# Tutorial_Sheet.net
KiCad netlist of a schematic drawn in Altium Designer
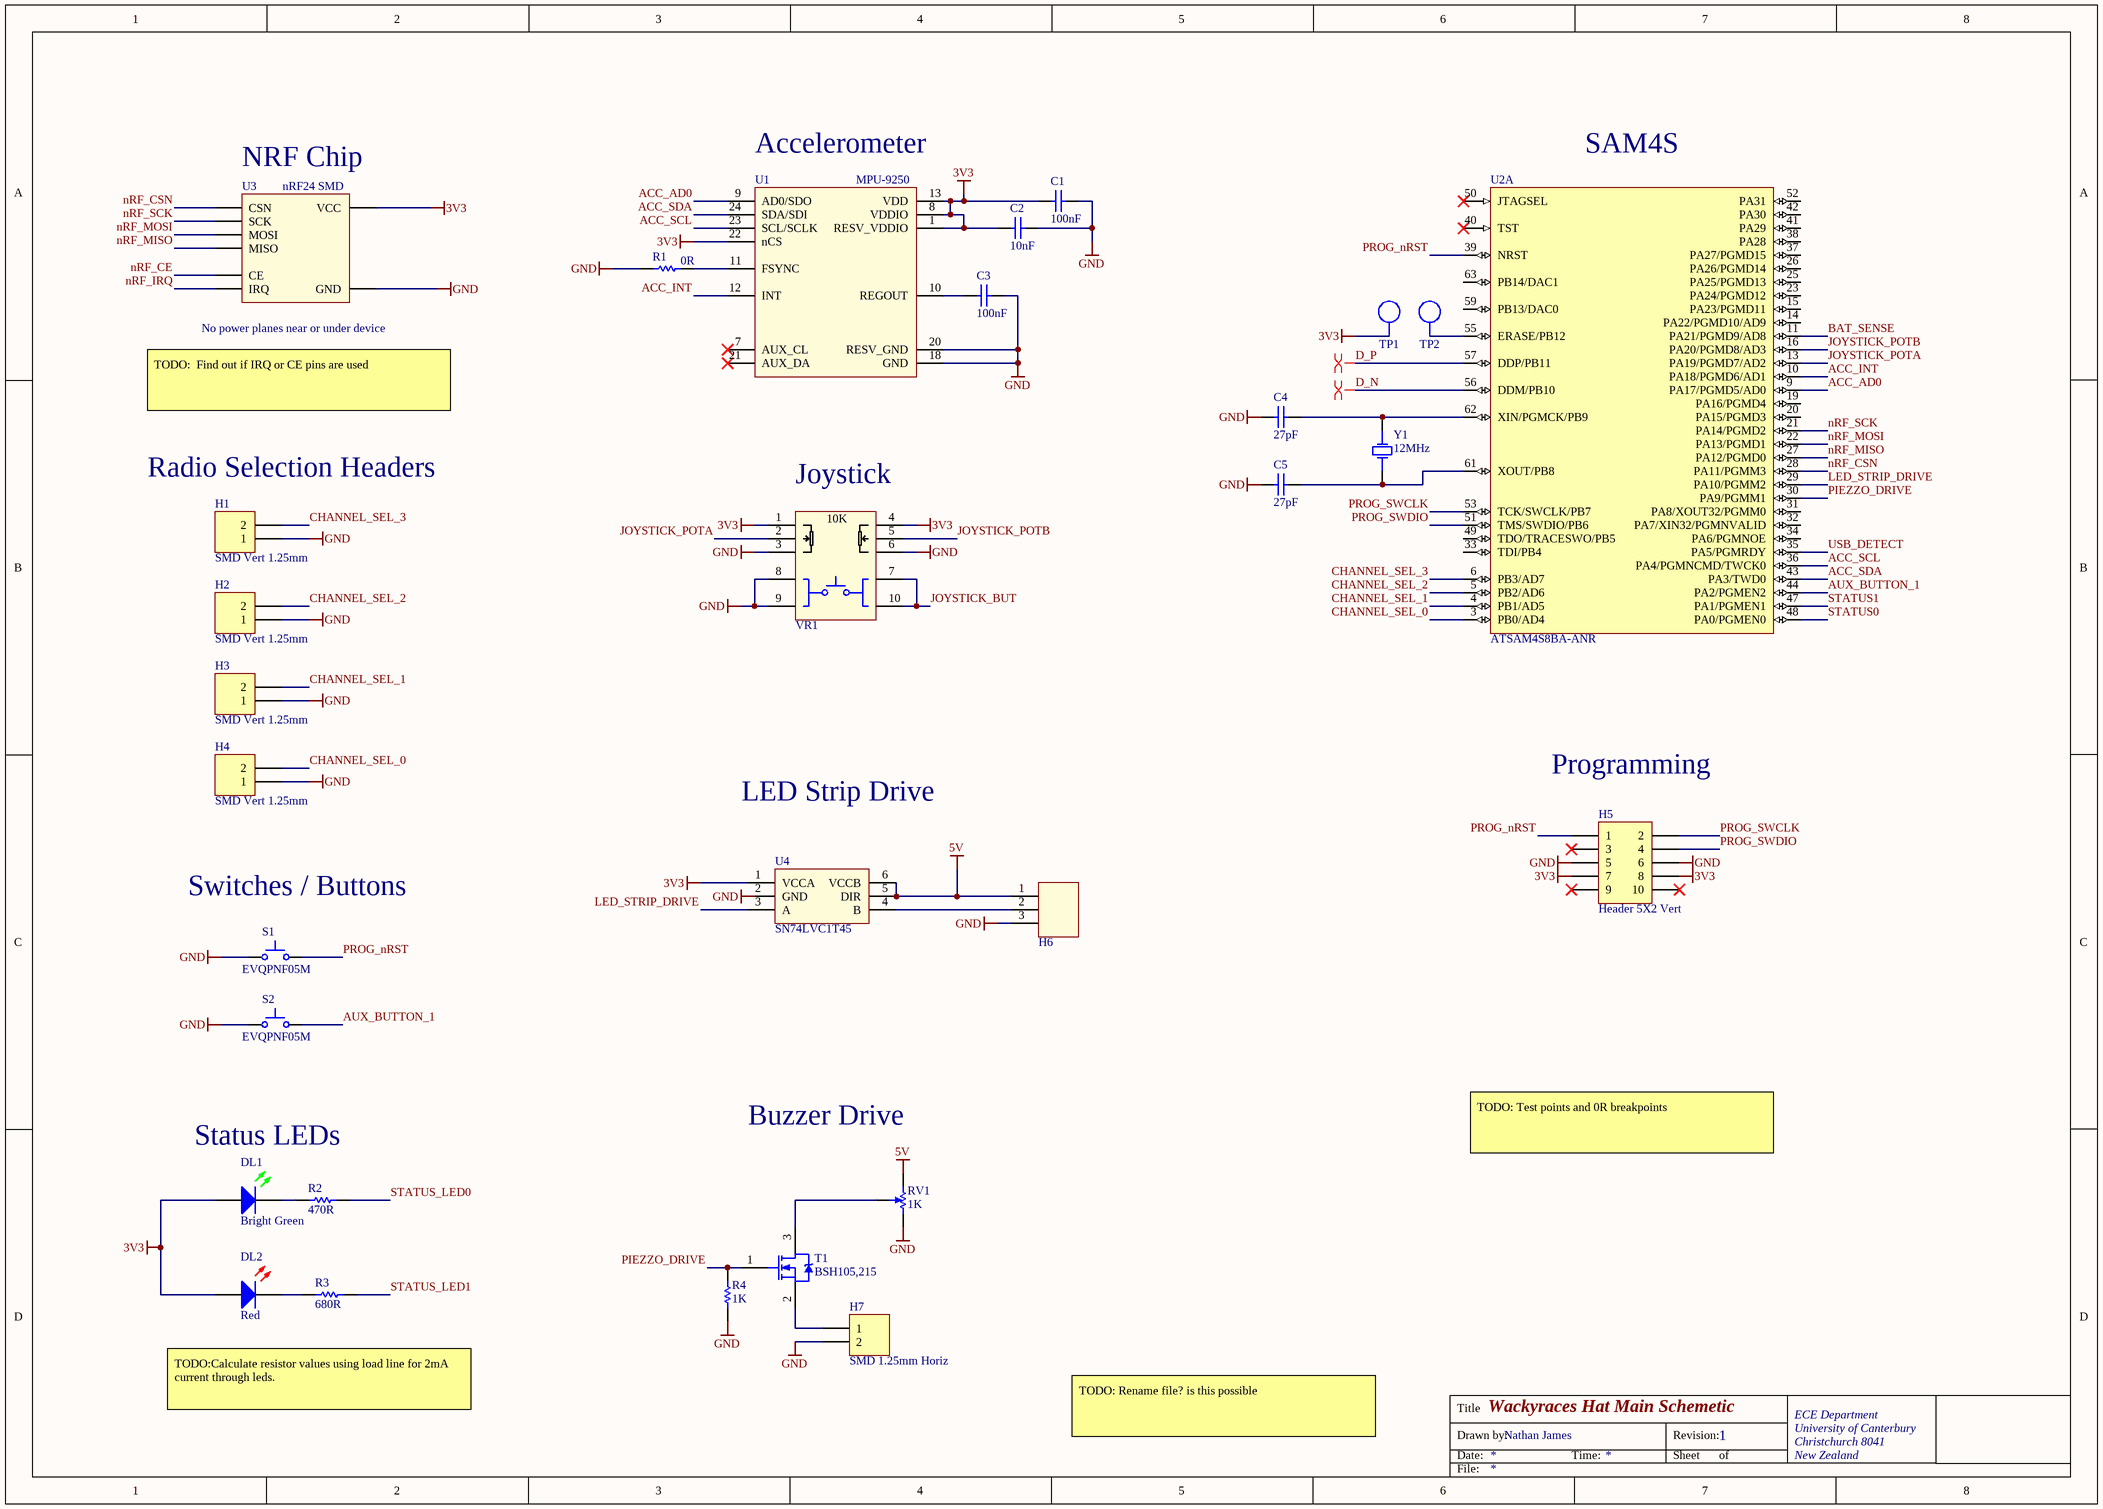
[diagram p0: Tutorial Sheet.SchDoc]

(export (version "E")
  (design (tool "Eeschema 10.0.6"))
  (components
    (comp (ref "C1")
      (value "100nF")
      (footprint "CAPC1608L")
      (description "CAP CER 100nF X7R +-10% 50V 0603")
      (libsource (lib "ECE AD19Components_19V1") (part "CC_100nF_0603"))
    )
    (comp (ref "C2")
      (value "10nF")
      (footprint "CAPC1608L")
      (description "CAP CER 10nF X7R +-10% 50V 0603")
      (libsource (lib "ECE AD19Components_19V1") (part "CC_10nF_0603"))
    )
    (comp (ref "C3")
      (value "100nF")
      (footprint "CAPC1608L")
      (description "CAP CER 100nF X7R +-10% 50V 0603")
      (libsource (lib "ECE AD19Components_19V1") (part "CC_100nF_0603"))
    )
    (comp (ref "C4")
      (value "27pF")
      (footprint "CAPC1608L")
      (description "CAP CER 27pF NPO/COG +-5% 50V 0603")
      (libsource (lib "ECE AD19Components_19V1") (part "CC_27pF_0603"))
    )
    (comp (ref "C5")
      (value "27pF")
      (footprint "CAPC1608L")
      (description "CAP CER 27pF NPO/COG +-5% 50V 0603")
      (libsource (lib "ECE AD19Components_19V1") (part "CC_27pF_0603"))
    )
    (comp (ref "DL1")
      (value "Bright Green")
      (footprint "WL-SMCW0603")
      (description "LED Bright Green 40mcd 0603 SMD")
      (fields
        (field (name "MANUFACTURER") "WURTH ELEKTRONIK")
        (field (name "MANUFACTURER PART NUMBER") "150060VS75000")
        (field (name "LED COLOUR") "Bright Green")
      )
      (libsource (lib "ECE AD19Components_19V1") (part "DL_150060VS75000"))
    )
    (comp (ref "DL2")
      (value "Red")
      (footprint "WL-SMCW0603")
      (description "LED Red 250mcd 0603 SMD")
      (fields
        (field (name "MANUFACTURER") "WURTH ELEKTRONIK")
        (field (name "MANUFACTURER PART NUMBER") "150060RS75000")
        (field (name "LED COLOUR") "Red")
      )
      (libsource (lib "ECE AD19Components_19V1") (part "DL_150060RS75000"))
    )
    (comp (ref "H1")
      (value "SMD Vert 1.25mm")
      (footprint "SD-53398-0219")
      (description "Header_Vert_2Pos_1.25mm_125V@1A_SMT")
      (fields
        (field (name "MANUFACTURER") "Molex Inc")
        (field (name "MANUFACTURER PART NUMBER") "0533980271")
      )
      (libsource (lib "ECE AD19Components_19V1") (part "JB_53398-02"))
    )
    (comp (ref "H2")
      (value "SMD Vert 1.25mm")
      (footprint "SD-53398-0219")
      (description "Header_Vert_2Pos_1.25mm_125V@1A_SMT")
      (fields
        (field (name "MANUFACTURER") "Molex Inc")
        (field (name "MANUFACTURER PART NUMBER") "0533980271")
      )
      (libsource (lib "ECE AD19Components_19V1") (part "JB_53398-02"))
    )
    (comp (ref "H3")
      (value "SMD Vert 1.25mm")
      (footprint "SD-53398-0219")
      (description "Header_Vert_2Pos_1.25mm_125V@1A_SMT")
      (fields
        (field (name "MANUFACTURER") "Molex Inc")
        (field (name "MANUFACTURER PART NUMBER") "0533980271")
      )
      (libsource (lib "ECE AD19Components_19V1") (part "JB_53398-02"))
    )
    (comp (ref "H4")
      (value "SMD Vert 1.25mm")
      (footprint "SD-53398-0219")
      (description "Header_Vert_2Pos_1.25mm_125V@1A_SMT")
      (fields
        (field (name "MANUFACTURER") "Molex Inc")
        (field (name "MANUFACTURER PART NUMBER") "0533980271")
      )
      (libsource (lib "ECE AD19Components_19V1") (part "JB_53398-02"))
    )
    (comp (ref "H5")
      (value "Header 5X2 Vert")
      (footprint "IDC2.54-V10D")
      (description "IDC Header, 2,54mm, 10-Pin, Vert")
      (libsource (lib "ECE AD19Components_19V1") (part "JA_HDR_IDC_5X2_VERT"))
    )
    (comp (ref "H6")
      (value "HEADER_3")
      (footprint "HEADER_3POS")
      (description "3Pin Header 2.54mm spacing")
      (libsource (lib "ENCE461AD19_19V2") (part "HEADER_3"))
    )
    (comp (ref "H7")
      (value "SMD 1.25mm Horiz")
      (footprint "SD-53261-0219")
      (description "Header_Horiz_2Pos_1.25mm_125V@1A_SMT")
      (fields (field (name "MANUFACTURER") "MOLEX") (field (name "MANUFACTURER PART NUMBER") "53261-0271"))
      (libsource (lib "ECE AD19Components_19V1") (part "JB_53261-02"))
    )
    (comp (ref "R1")
      (value "0R")
      (footprint "RESC1608L")
      (description "RES 0.0 OHM 1/10W 5% 0603 SMD")
      (libsource (lib "ECE AD19Components_19V1") (part "RS_0R0"))
    )
    (comp (ref "R2")
      (value "470R")
      (footprint "RESC1608L")
      (description "RES 470 OHM 1/10W 5% 0603 SMD")
      (libsource (lib "ECE AD19Components_19V1") (part "RS_470R"))
    )
    (comp (ref "R3")
      (value "680R")
      (footprint "RESC3216L")
      (description "RES 680R OHM 1/4W 5% 1206 SMD")
      (libsource (lib "ECE AD19Components_19V1") (part "RT_680R"))
    )
    (comp (ref "R4")
      (value "1K")
      (footprint "RESC1608L")
      (description "RES 1.0K OHM 1/10W 5% 0603 SMD")
      (libsource (lib "ECE AD19Components_19V1") (part "RS_1K"))
    )
    (comp (ref "RV1")
      (value "1K")
      (footprint "PVZ2A")
      (description "Trim Pot SMD 1K Murata PVZ2 Series SMD")
      (fields
        (field (name "MANUFACTURER") "MURATA")
        (field (name "MANUFACTURER PART NUMBER") "PVZ2A102C04B00")
      )
      (libsource (lib "ECE AD19Components_19V1") (part "RM_1K"))
    )
    (comp (ref "S1")
      (value "EVQPNF05M")
      (footprint "EVQPNF05M")
      (description "Panasonic 6 x 3.5mm SMD Light Touch Switch Type SMD")
      (fields (field (name "MANUFACTURER") "Panasonic"))
      (libsource (lib "ECE AD19Components_19V1") (part "WS_EVQPNF05M"))
    )
    (comp (ref "S2")
      (value "EVQPNF05M")
      (footprint "EVQPNF05M")
      (description "Panasonic 6 x 3.5mm SMD Light Touch Switch Type SMD")
      (fields (field (name "MANUFACTURER") "Panasonic"))
      (libsource (lib "ECE AD19Components_19V1") (part "WS_EVQPNF05M"))
    )
    (comp (ref "T1")
      (value "BSH105,215")
      (footprint "SOT23_L")
      (description "MOSFET N-CH 20V 1.05A SOT-23")
      (fields
        (field (name "MANUFACTURER") "NXP Semiconductors")
        (field (name "MANUFACTURER PART NUMBER") "BSH105,215")
      )
      (libsource (lib "ECE AD19Components_19V1") (part "TM_BSH105"))
    )
    (comp (ref "TP1")
      (value "Erase")
      (footprint "TP_1206")
      (description "Test-Point 3.3x1.6x2.1mm SMD")
      (fields
        (field (name "MANUFACTURER") "Harwin Inc")
        (field (name "MANUFACTURER PART NUMBER") "S1751-46R")
      )
      (libsource (lib "ECE AD19Components_19V1") (part "TP_1206"))
    )
    (comp (ref "TP2")
      (value "Erase")
      (footprint "TP_1206")
      (description "Test-Point 3.3x1.6x2.1mm SMD")
      (fields
        (field (name "MANUFACTURER") "Harwin Inc")
        (field (name "MANUFACTURER PART NUMBER") "S1751-46R")
      )
      (libsource (lib "ECE AD19Components_19V1") (part "TP_1206"))
    )
    (comp (ref "U1")
      (value "MPU-9250")
      (footprint "Quad24")
      (description "9 axis IMU")
      (libsource (lib "ENCE461AD19_19V2") (part "MPU-9250"))
    )
    (comp (ref "U2")
      (value "ATSAM4S8BA-ANR")
      (footprint "LQFP64_L")
      (description "IC MCU 32BIT 512KB FLASH 64LQFP")
      (fields (field (name "MANUFACTURER") "Atmel"))
      (libsource (lib "ECE AD19Components_19V1") (part "SE_ATSAM4S16BA-MU"))
    )
    (comp (ref "U3")
      (value "nRF24 SMD")
      (footprint "NRF24")
      (description "nRF24 SMD Module")
      (fields (field (name "WARNING") "No power planes near or under device"))
      (libsource (lib "ENCE461AD19_19V2") (part "NRF24"))
    )
    (comp (ref "U4")
      (value "SN74LVC1T45")
      (footprint "SOT23-6_N")
      (description "1.8V - 5V level converter")
      (libsource (lib "ENCE461_extras_2020") (part "SN74LVC1T45"))
    )
    (comp (ref "VR1")
      (value "Joystick 10k with Sw")
      (footprint "Joystick_Sw")
      (description "JOYSTICK 10K OHM 2 AXIS TH")
      (libsource (lib "ENCE461AD19_19V2") (part "Joystick 10k with Sw"))
    )
    (comp (ref "Y1")
      (value "12MHz")
      (footprint "6.0X3.5-4")
      (description "CRYSTAL 12MHZ 18PF 6X3.5mm SMD")
      (fields
        (field (name "MANUFACTURER") "CTS-Frequency Controls")
        (field (name "MANUFACTURER PART NUMBER") "406C35D12M00000")
        (field (name "FREQUENCY") "12MHz")
      )
      (libsource (lib "ECE AD19Components_19V1") (part "XT_CRYSTAL_12MHz_18pF"))
    )
  )
  (nets
    (net (code "1") (name "/ACC_AD0") (class "Default")
      (node (ref "U1") (pin "9") (pinfunction "AD0/SDO_9") (pintype "passive"))
      (node (ref "U2") (pin "9") (pinfunction "PA17/PGMD5/AD0_9") (pintype "bidirectional"))
    )
    (net (code "2") (name "/ACC_INT") (class "Default")
      (node (ref "U1") (pin "12") (pinfunction "INT_12") (pintype "passive"))
      (node (ref "U2") (pin "10") (pinfunction "PA18/PGMD6/AD1_10") (pintype "bidirectional"))
    )
    (net (code "3") (name "/ACC_SCL") (class "Default")
      (node (ref "U1") (pin "23") (pinfunction "SCL/SCLK_23") (pintype "passive"))
      (node (ref "U2") (pin "36") (pinfunction "PA4/PGMNCMD/TWCK0_36") (pintype "bidirectional"))
    )
    (net (code "4") (name "/ACC_SDA") (class "Default")
      (node (ref "U1") (pin "24") (pinfunction "SDA/SDI_24") (pintype "passive"))
      (node (ref "U2") (pin "43") (pinfunction "PA3/TWD0_43") (pintype "bidirectional"))
    )
    (net (code "5") (name "/AUX_BUTTON_1") (class "Default")
      (node (ref "S2") (pin "2") (pintype "passive"))
      (node (ref "U2") (pin "44") (pinfunction "PA2/PGMEN2_44") (pintype "bidirectional"))
    )
    (net (code "6") (name "/BAT_SENSE") (class "Default")
      (node (ref "U2") (pin "11") (pinfunction "PA21/PGMD9/AD8_11") (pintype "bidirectional"))
    )
    (net (code "7") (name "/CHANNEL_SEL_0") (class "Default")
      (node (ref "H4") (pin "2") (pinfunction "2_2") (pintype "passive"))
      (node (ref "U2") (pin "3") (pinfunction "PB0/AD4_3") (pintype "bidirectional"))
    )
    (net (code "8") (name "/CHANNEL_SEL_1") (class "Default")
      (node (ref "H3") (pin "2") (pinfunction "2_2") (pintype "passive"))
      (node (ref "U2") (pin "4") (pinfunction "PB1/AD5_4") (pintype "bidirectional"))
    )
    (net (code "9") (name "/CHANNEL_SEL_2") (class "Default")
      (node (ref "H2") (pin "2") (pinfunction "2_2") (pintype "passive"))
      (node (ref "U2") (pin "5") (pinfunction "PB2/AD6_5") (pintype "bidirectional"))
    )
    (net (code "10") (name "/CHANNEL_SEL_3") (class "Default")
      (node (ref "H1") (pin "2") (pinfunction "2_2") (pintype "passive"))
      (node (ref "U2") (pin "6") (pinfunction "PB3/AD7_6") (pintype "bidirectional"))
    )
    (net (code "11") (name "/D_N") (class "Default")
      (node (ref "U2") (pin "56") (pinfunction "DDM/PB10_56") (pintype "bidirectional"))
    )
    (net (code "12") (name "/D_P") (class "Default")
      (node (ref "U2") (pin "57") (pinfunction "DDP/PB11_57") (pintype "bidirectional"))
    )
    (net (code "13") (name "/JOYSTICK_BUT") (class "Default")
      (node (ref "VR1") (pin "10") (pinfunction "10_10") (pintype "passive"))
      (node (ref "VR1") (pin "7") (pinfunction "7_7") (pintype "passive"))
    )
    (net (code "14") (name "/JOYSTICK_POTA") (class "Default")
      (node (ref "U2") (pin "13") (pinfunction "PA19/PGMD7/AD2_13") (pintype "bidirectional"))
      (node (ref "VR1") (pin "2") (pinfunction "2_2") (pintype "passive"))
    )
    (net (code "15") (name "/JOYSTICK_POTB") (class "Default")
      (node (ref "U2") (pin "16") (pinfunction "PA20/PGMD8/AD3_16") (pintype "bidirectional"))
      (node (ref "VR1") (pin "5") (pinfunction "2'_5") (pintype "passive"))
    )
    (net (code "16") (name "/LED_STRIP_DRIVE") (class "Default")
      (node (ref "U2") (pin "29") (pinfunction "PA10/PGMM2_29") (pintype "bidirectional"))
      (node (ref "U4") (pin "3") (pinfunction "A_3") (pintype "passive"))
    )
    (net (code "17") (name "/PIEZZO_DRIVE") (class "Default")
      (node (ref "R4") (pin "2") (pinfunction "2_2") (pintype "passive"))
      (node (ref "T1") (pin "1") (pinfunction "1_1") (pintype "passive"))
      (node (ref "U2") (pin "30") (pinfunction "PA9/PGMM1_30") (pintype "bidirectional"))
    )
    (net (code "18") (name "/PROG_SWCLK") (class "Default")
      (node (ref "H5") (pin "2") (pinfunction "2_2") (pintype "passive"))
      (node (ref "U2") (pin "53") (pinfunction "TCK/SWCLK/PB7_53") (pintype "bidirectional"))
    )
    (net (code "19") (name "/PROG_SWDIO") (class "Default")
      (node (ref "H5") (pin "4") (pinfunction "4_4") (pintype "passive"))
      (node (ref "U2") (pin "51") (pinfunction "TMS/SWDIO/PB6_51") (pintype "bidirectional"))
    )
    (net (code "20") (name "/PROG_nRST") (class "Default")
      (node (ref "H5") (pin "1") (pinfunction "1_1") (pintype "passive"))
      (node (ref "S1") (pin "2") (pintype "passive"))
      (node (ref "U2") (pin "39") (pinfunction "NRST_39") (pintype "bidirectional"))
    )
    (net (code "21") (name "/STATUS0") (class "Default")
      (node (ref "U2") (pin "48") (pinfunction "PA0/PGMEN0_48") (pintype "bidirectional"))
    )
    (net (code "22") (name "/STATUS1") (class "Default")
      (node (ref "U2") (pin "47") (pinfunction "PA1/PGMEN1_47") (pintype "bidirectional"))
    )
    (net (code "23") (name "/STATUS_LED0") (class "Default")
      (node (ref "R2") (pin "2") (pinfunction "2_2") (pintype "passive"))
    )
    (net (code "24") (name "/STATUS_LED1") (class "Default")
      (node (ref "R3") (pin "2") (pinfunction "2_2") (pintype "passive"))
    )
    (net (code "25") (name "/USB_DETECT") (class "Default")
      (node (ref "U2") (pin "35") (pinfunction "PA5/PGMRDY_35") (pintype "bidirectional"))
    )
    (net (code "26") (name "/nRF_CE") (class "Default")
      (node (ref "U3") (pin "3") (pinfunction "CE_3") (pintype "passive"))
    )
    (net (code "27") (name "/nRF_CSN") (class "Default")
      (node (ref "U2") (pin "28") (pinfunction "PA11/PGMM3_28") (pintype "bidirectional"))
      (node (ref "U3") (pin "4") (pinfunction "CSN_4") (pintype "passive"))
    )
    (net (code "28") (name "/nRF_IRQ") (class "Default")
      (node (ref "U3") (pin "8") (pinfunction "IRQ_8") (pintype "passive"))
    )
    (net (code "29") (name "/nRF_MISO") (class "Default")
      (node (ref "U2") (pin "27") (pinfunction "PA12/PGMD0_27") (pintype "bidirectional"))
      (node (ref "U3") (pin "7") (pinfunction "MISO_7") (pintype "passive"))
    )
    (net (code "30") (name "/nRF_MOSI") (class "Default")
      (node (ref "U2") (pin "22") (pinfunction "PA13/PGMD1_22") (pintype "bidirectional"))
      (node (ref "U3") (pin "6") (pinfunction "MOSI_6") (pintype "passive"))
    )
    (net (code "31") (name "/nRF_SCK") (class "Default")
      (node (ref "U2") (pin "21") (pinfunction "PA14/PGMD2_21") (pintype "bidirectional"))
      (node (ref "U3") (pin "5") (pinfunction "SCK_5") (pintype "passive"))
    )
    (net (code "32") (name "3V3") (class "Default")
      (node (ref "C1") (pin "1") (pinfunction "1_1") (pintype "passive"))
      (node (ref "C2") (pin "1") (pinfunction "1_1") (pintype "passive"))
      (node (ref "DL1") (pin "2") (pinfunction "A_2") (pintype "passive"))
      (node (ref "DL2") (pin "2") (pinfunction "A_2") (pintype "passive"))
      (node (ref "H5") (pin "7") (pinfunction "7_7") (pintype "passive"))
      (node (ref "H5") (pin "8") (pinfunction "8_8") (pintype "passive"))
      (node (ref "TP1") (pin "1") (pinfunction "1_1") (pintype "passive"))
      (node (ref "U1") (pin "1") (pinfunction "RESV_VDDIO_1") (pintype "passive"))
      (node (ref "U1") (pin "13") (pinfunction "VDD_13") (pintype "passive"))
      (node (ref "U1") (pin "22") (pinfunction "nCS_22") (pintype "passive"))
      (node (ref "U1") (pin "8") (pinfunction "VDDIO_8") (pintype "passive"))
      (node (ref "U3") (pin "1") (pinfunction "VCC_1") (pintype "passive"))
      (node (ref "U4") (pin "1") (pinfunction "VCCA_1") (pintype "passive"))
      (node (ref "VR1") (pin "1") (pinfunction "1_1") (pintype "passive"))
      (node (ref "VR1") (pin "4") (pinfunction "1'_4") (pintype "passive"))
    )
    (net (code "33") (name "5V") (class "Default")
      (node (ref "H6") (pin "1") (pintype "passive"))
      (node (ref "RV1") (pin "3") (pinfunction "-_3") (pintype "passive"))
      (node (ref "U4") (pin "5") (pinfunction "DIR_5") (pintype "passive"))
      (node (ref "U4") (pin "6") (pinfunction "VCCB_6") (pintype "passive"))
    )
    (net (code "34") (name "GND") (class "Default")
      (node (ref "C1") (pin "2") (pinfunction "2_2") (pintype "passive"))
      (node (ref "C2") (pin "2") (pinfunction "2_2") (pintype "passive"))
      (node (ref "C3") (pin "2") (pinfunction "2_2") (pintype "passive"))
      (node (ref "C4") (pin "1") (pinfunction "1_1") (pintype "passive"))
      (node (ref "C5") (pin "1") (pinfunction "1_1") (pintype "passive"))
      (node (ref "H1") (pin "1") (pinfunction "1_1") (pintype "passive"))
      (node (ref "H2") (pin "1") (pinfunction "1_1") (pintype "passive"))
      (node (ref "H3") (pin "1") (pinfunction "1_1") (pintype "passive"))
      (node (ref "H4") (pin "1") (pinfunction "1_1") (pintype "passive"))
      (node (ref "H5") (pin "5") (pinfunction "5_5") (pintype "passive"))
      (node (ref "H5") (pin "6") (pinfunction "6_6") (pintype "passive"))
      (node (ref "H6") (pin "3") (pintype "passive"))
      (node (ref "H7") (pin "2") (pinfunction "2_2") (pintype "passive"))
      (node (ref "R1") (pin "1") (pinfunction "1_1") (pintype "passive"))
      (node (ref "R4") (pin "1") (pinfunction "1_1") (pintype "passive"))
      (node (ref "RV1") (pin "1") (pinfunction "1_1") (pintype "passive"))
      (node (ref "S1") (pin "1") (pintype "passive"))
      (node (ref "S2") (pin "1") (pintype "passive"))
      (node (ref "U1") (pin "18") (pinfunction "GND_18") (pintype "passive"))
      (node (ref "U1") (pin "20") (pinfunction "RESV_GND_20") (pintype "passive"))
      (node (ref "U3") (pin "2") (pinfunction "GND_2") (pintype "passive"))
      (node (ref "VR1") (pin "3") (pinfunction "3_3") (pintype "passive"))
      (node (ref "VR1") (pin "6") (pinfunction "3'_6") (pintype "passive"))
      (node (ref "VR1") (pin "8") (pinfunction "8_8") (pintype "passive"))
      (node (ref "VR1") (pin "9") (pinfunction "9_9") (pintype "passive"))
    )
    (net (code "35") (name "Net-(DL1-K)") (class "Default")
      (node (ref "DL1") (pin "1") (pinfunction "K_1") (pintype "passive"))
      (node (ref "R2") (pin "1") (pinfunction "1_1") (pintype "passive"))
    )
    (net (code "36") (name "Net-(DL2-K)") (class "Default")
      (node (ref "DL2") (pin "1") (pinfunction "K_1") (pintype "passive"))
      (node (ref "R3") (pin "1") (pinfunction "1_1") (pintype "passive"))
    )
    (net (code "37") (name "Net-(H7-Pad1)") (class "Default")
      (node (ref "H7") (pin "1") (pinfunction "1_1") (pintype "passive"))
      (node (ref "T1") (pin "2") (pinfunction "2_2") (pintype "passive"))
    )
    (net (code "38") (name "Net-(RV1-W)") (class "Default")
      (node (ref "RV1") (pin "2") (pinfunction "W_2") (pintype "passive"))
      (node (ref "T1") (pin "3") (pinfunction "3_3") (pintype "passive"))
    )
    (net (code "39") (name "Net-(U1-FSYNC)") (class "Default")
      (node (ref "R1") (pin "2") (pinfunction "2_2") (pintype "passive"))
      (node (ref "U1") (pin "11") (pinfunction "FSYNC_11") (pintype "passive"))
    )
    (net (code "40") (name "Net-(U1-REGOUT)") (class "Default")
      (node (ref "C3") (pin "1") (pinfunction "1_1") (pintype "passive"))
      (node (ref "U1") (pin "10") (pinfunction "REGOUT_10") (pintype "passive"))
    )
    (net (code "41") (name "Net-(U2A-ERASE{slash}PB12)") (class "Default")
      (node (ref "TP2") (pin "1") (pinfunction "1_1") (pintype "passive"))
      (node (ref "U2") (pin "55") (pinfunction "ERASE/PB12_55") (pintype "bidirectional"))
    )
    (net (code "42") (name "Net-(U2A-XIN{slash}PGMCK{slash}PB9)") (class "Default")
      (node (ref "C4") (pin "2") (pinfunction "2_2") (pintype "passive"))
      (node (ref "U2") (pin "62") (pinfunction "XIN/PGMCK/PB9_62") (pintype "bidirectional"))
      (node (ref "Y1") (pin "3") (pinfunction "OSC2_3") (pintype "passive"))
    )
    (net (code "43") (name "Net-(U2A-XOUT{slash}PB8)") (class "Default")
      (node (ref "C5") (pin "2") (pinfunction "2_2") (pintype "passive"))
      (node (ref "U2") (pin "61") (pinfunction "XOUT/PB8_61") (pintype "bidirectional"))
      (node (ref "Y1") (pin "1") (pinfunction "OSC1_1") (pintype "passive"))
    )
    (net (code "44") (name "Net-(U4-B)") (class "Default")
      (node (ref "H6") (pin "2") (pintype "passive"))
      (node (ref "U4") (pin "4") (pinfunction "B_4") (pintype "passive"))
    )
    (net (code "45") (name "unconnected-(H5-Pad3)") (class "Default")
      (node (ref "H5") (pin "3") (pinfunction "3_3") (pintype "passive+no_connect"))
    )
    (net (code "46") (name "unconnected-(H5-Pad9)") (class "Default")
      (node (ref "H5") (pin "9") (pinfunction "9_9") (pintype "passive+no_connect"))
    )
    (net (code "47") (name "unconnected-(H5-Pad10)") (class "Default")
      (node (ref "H5") (pin "10") (pinfunction "10_10") (pintype "passive+no_connect"))
    )
    (net (code "48") (name "unconnected-(U1-AUX_CL-Pad7)") (class "Default")
      (node (ref "U1") (pin "7") (pinfunction "AUX_CL_7") (pintype "passive+no_connect"))
    )
    (net (code "49") (name "unconnected-(U1-AUX_DA-Pad21)") (class "Default")
      (node (ref "U1") (pin "21") (pinfunction "AUX_DA_21") (pintype "passive+no_connect"))
    )
    (net (code "50") (name "unconnected-(U2A-JTAGSEL-Pad50)") (class "Default")
      (node (ref "U2") (pin "50") (pinfunction "JTAGSEL_50") (pintype "input+no_connect"))
    )
    (net (code "51") (name "unconnected-(U2A-PA6{slash}PGMNOE-Pad34)") (class "Default")
      (node (ref "U2") (pin "34") (pinfunction "PA6/PGMNOE_34") (pintype "bidirectional"))
    )
    (net (code "52") (name "unconnected-(U2A-PA7{slash}XIN32{slash}PGMNVALID-Pad32)") (class "Default")
      (node (ref "U2") (pin "32") (pinfunction "PA7/XIN32/PGMNVALID_32") (pintype "bidirectional"))
    )
    (net (code "53") (name "unconnected-(U2A-PA8{slash}XOUT32{slash}PGMM0-Pad31)") (class "Default")
      (node (ref "U2") (pin "31") (pinfunction "PA8/XOUT32/PGMM0_31") (pintype "bidirectional"))
    )
    (net (code "54") (name "unconnected-(U2A-PA15{slash}PGMD3-Pad20)") (class "Default")
      (node (ref "U2") (pin "20") (pinfunction "PA15/PGMD3_20") (pintype "bidirectional"))
    )
    (net (code "55") (name "unconnected-(U2A-PA16{slash}PGMD4-Pad19)") (class "Default")
      (node (ref "U2") (pin "19") (pinfunction "PA16/PGMD4_19") (pintype "bidirectional"))
    )
    (net (code "56") (name "unconnected-(U2A-PA22{slash}PGMD10{slash}AD9-Pad14)") (class "Default")
      (node (ref "U2") (pin "14") (pinfunction "PA22/PGMD10/AD9_14") (pintype "bidirectional"))
    )
    (net (code "57") (name "unconnected-(U2A-PA23{slash}PGMD11-Pad15)") (class "Default")
      (node (ref "U2") (pin "15") (pinfunction "PA23/PGMD11_15") (pintype "bidirectional"))
    )
    (net (code "58") (name "unconnected-(U2A-PA24{slash}PGMD12-Pad23)") (class "Default")
      (node (ref "U2") (pin "23") (pinfunction "PA24/PGMD12_23") (pintype "bidirectional"))
    )
    (net (code "59") (name "unconnected-(U2A-PA25{slash}PGMD13-Pad25)") (class "Default")
      (node (ref "U2") (pin "25") (pinfunction "PA25/PGMD13_25") (pintype "bidirectional"))
    )
    (net (code "60") (name "unconnected-(U2A-PA26{slash}PGMD14-Pad26)") (class "Default")
      (node (ref "U2") (pin "26") (pinfunction "PA26/PGMD14_26") (pintype "bidirectional"))
    )
    (net (code "61") (name "unconnected-(U2A-PA27{slash}PGMD15-Pad37)") (class "Default")
      (node (ref "U2") (pin "37") (pinfunction "PA27/PGMD15_37") (pintype "bidirectional"))
    )
    (net (code "62") (name "unconnected-(U2A-PA28-Pad38)") (class "Default")
      (node (ref "U2") (pin "38") (pinfunction "PA28_38") (pintype "bidirectional"))
    )
    (net (code "63") (name "unconnected-(U2A-PA29-Pad41)") (class "Default")
      (node (ref "U2") (pin "41") (pinfunction "PA29_41") (pintype "bidirectional"))
    )
    (net (code "64") (name "unconnected-(U2A-PA30-Pad42)") (class "Default")
      (node (ref "U2") (pin "42") (pinfunction "PA30_42") (pintype "bidirectional"))
    )
    (net (code "65") (name "unconnected-(U2A-PA31-Pad52)") (class "Default")
      (node (ref "U2") (pin "52") (pinfunction "PA31_52") (pintype "bidirectional"))
    )
    (net (code "66") (name "unconnected-(U2A-PB13{slash}DAC0-Pad59)") (class "Default")
      (node (ref "U2") (pin "59") (pinfunction "PB13/DAC0_59") (pintype "bidirectional"))
    )
    (net (code "67") (name "unconnected-(U2A-PB14{slash}DAC1-Pad63)") (class "Default")
      (node (ref "U2") (pin "63") (pinfunction "PB14/DAC1_63") (pintype "bidirectional"))
    )
    (net (code "68") (name "unconnected-(U2A-TDI{slash}PB4-Pad33)") (class "Default")
      (node (ref "U2") (pin "33") (pinfunction "TDI/PB4_33") (pintype "bidirectional"))
    )
    (net (code "69") (name "unconnected-(U2A-TDO{slash}TRACESWO{slash}PB5-Pad49)") (class "Default")
      (node (ref "U2") (pin "49") (pinfunction "TDO/TRACESWO/PB5_49") (pintype "bidirectional"))
    )
    (net (code "70") (name "unconnected-(U2A-TST-Pad40)") (class "Default")
      (node (ref "U2") (pin "40") (pinfunction "TST_40") (pintype "input+no_connect"))
    )
    (net (code "71") (name "unconnected-(U4-GND-Pad2)") (class "Default")
      (node (ref "U4") (pin "2") (pinfunction "GND_2") (pintype "passive"))
    )
  )
)
